# source_eagle.net
KiCad netlist of a schematic drawn in EAGLE
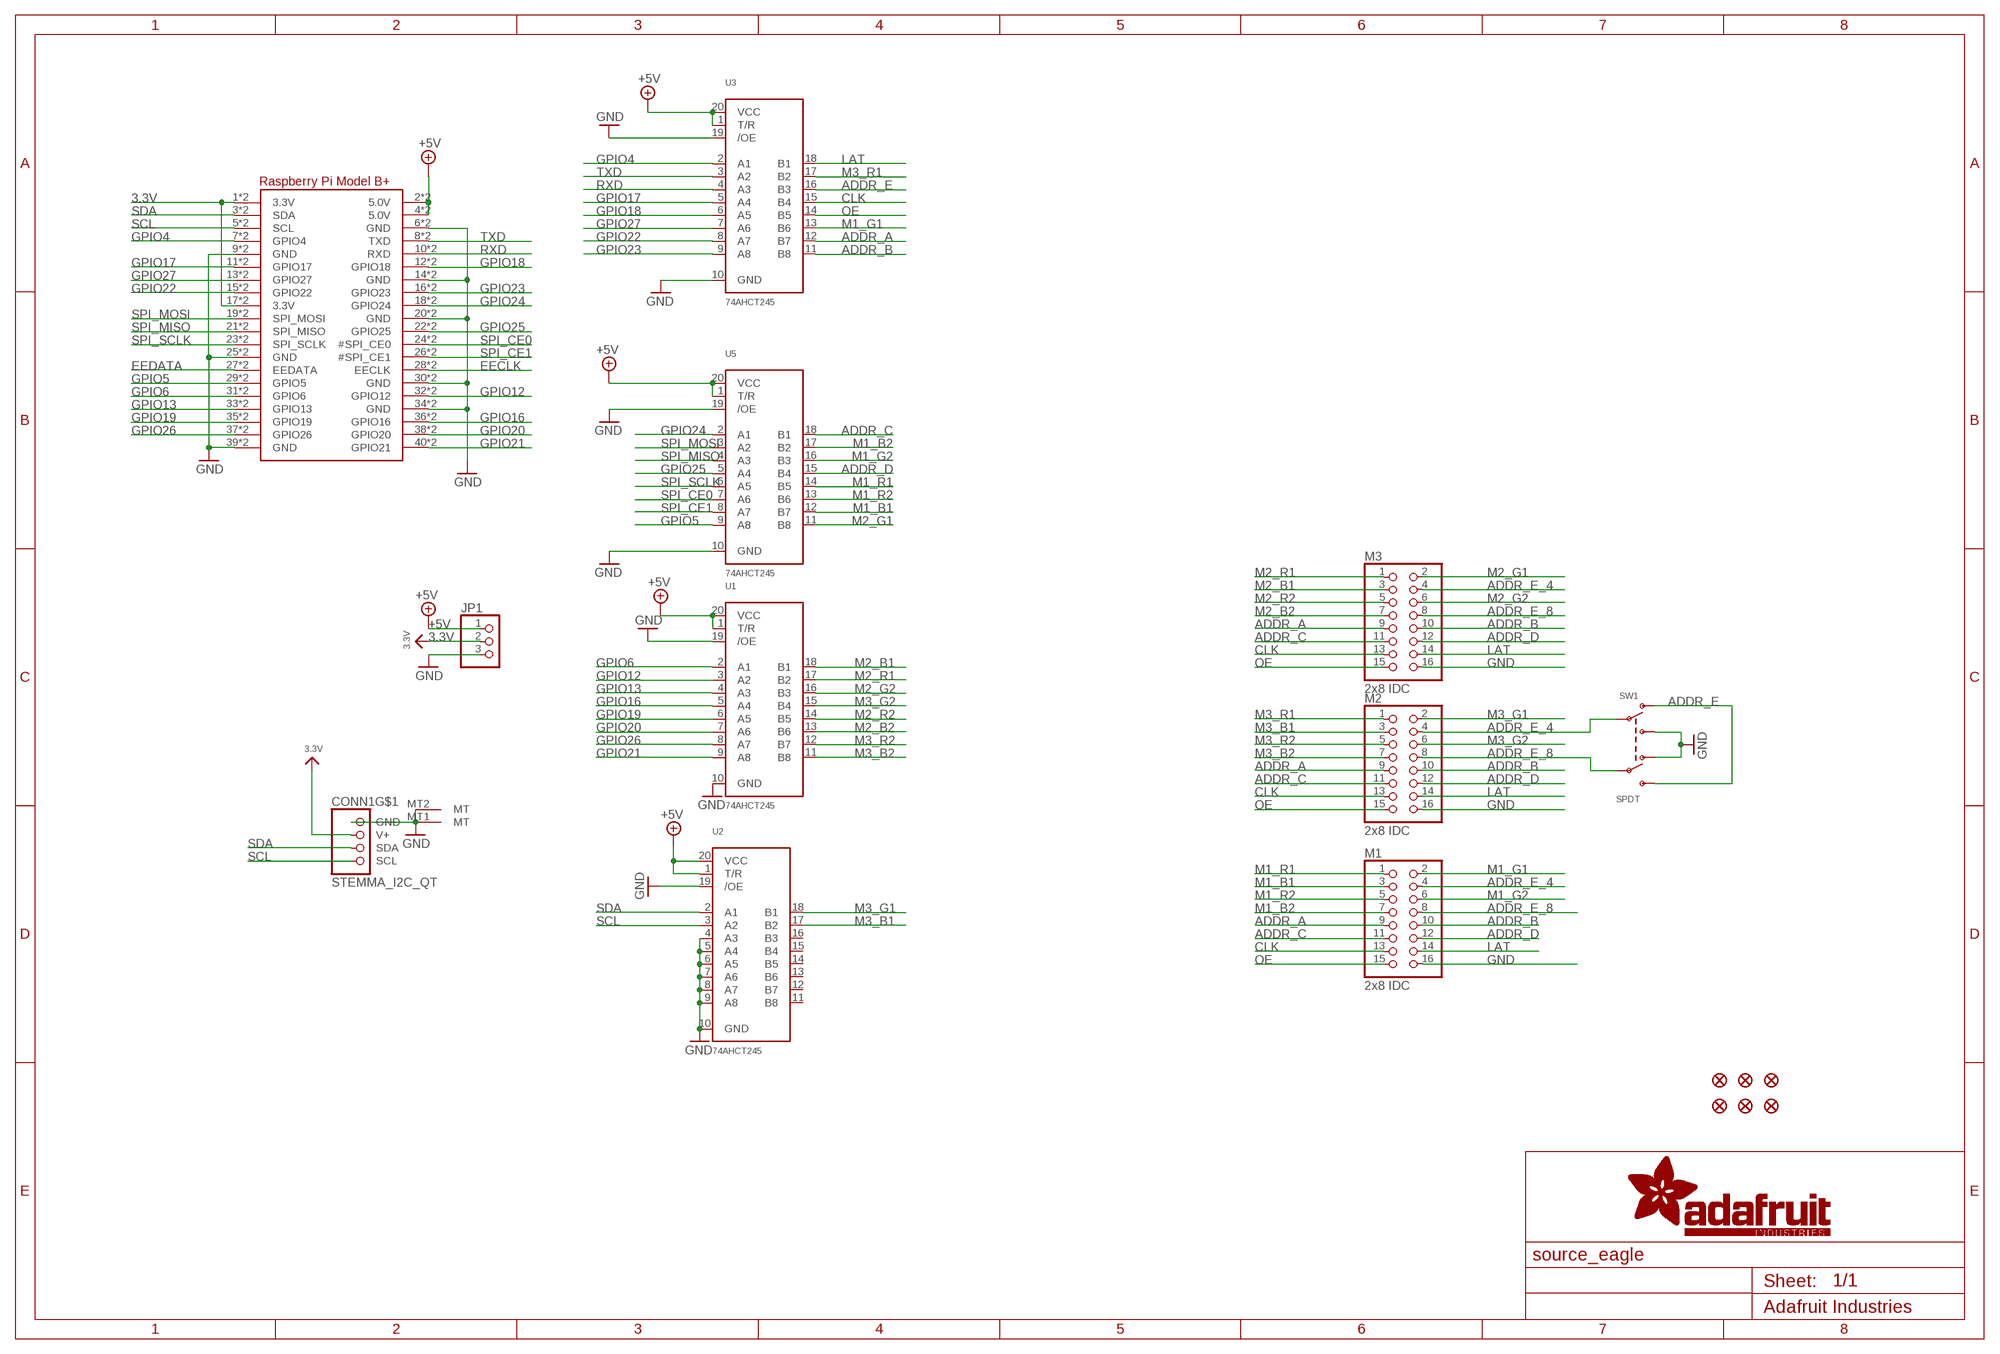
[diagram p0: schematic, sheet 1]

(export (version "E")
  (design (tool "Eeschema 10.0.6"))
  (components
    (comp (ref "CONN1")
      (value "STEMMA_I2C_QT")
      (footprint "eagle-import:JST_SH4")
      (libsource (lib "eagle-import") (part "STEMMA_I2C_QT"))
    )
    (comp (ref "FID1")
      (value "FIDUCIAL_1MM")
      (footprint "eagle-import:FIDUCIAL_1MM")
      (libsource (lib "eagle-import") (part "FIDUCIAL_1MM"))
    )
    (comp (ref "FID2")
      (value "FIDUCIAL_1MM")
      (footprint "eagle-import:FIDUCIAL_1MM")
      (libsource (lib "eagle-import") (part "FIDUCIAL_1MM"))
    )
    (comp (ref "FID3")
      (value "FIDUCIAL_1MM")
      (footprint "eagle-import:FIDUCIAL_1MM")
      (libsource (lib "eagle-import") (part "FIDUCIAL_1MM"))
    )
    (comp (ref "FID4")
      (value "FIDUCIAL_1MM")
      (footprint "eagle-import:FIDUCIAL_1MM")
      (libsource (lib "eagle-import") (part "FIDUCIAL_1MM"))
    )
    (comp (ref "FID5")
      (value "FIDUCIAL_1MM")
      (footprint "eagle-import:FIDUCIAL_1MM")
      (libsource (lib "eagle-import") (part "FIDUCIAL_1MM"))
    )
    (comp (ref "FID6")
      (value "FIDUCIAL_1MM")
      (footprint "eagle-import:FIDUCIAL_1MM")
      (libsource (lib "eagle-import") (part "FIDUCIAL_1MM"))
    )
    (comp (ref "JP1")
      (value "HEADER-1X376MIL")
      (footprint "eagle-import:1X03_ROUND_76")
      (libsource (lib "eagle-import") (part "HEADER-1X376MIL"))
    )
    (comp (ref "M1")
      (value "2x8 IDC")
      (footprint "eagle-import:2X08_SHROUDED")
      (libsource (lib "eagle-import") (part "HEADER-2X8_SHROUDED"))
    )
    (comp (ref "M2")
      (value "2x8 IDC")
      (footprint "eagle-import:2X08_SHROUDED")
      (libsource (lib "eagle-import") (part "HEADER-2X8_SHROUDED"))
    )
    (comp (ref "M3")
      (value "2x8 IDC")
      (footprint "eagle-import:2X08_SHROUDED")
      (libsource (lib "eagle-import") (part "HEADER-2X8_SHROUDED"))
    )
    (comp (ref "RPI1")
      (value "RASPBERRYPI_BPLUS_2X20_THMSMT")
      (footprint "eagle-import:RASPI_2X20_THMSMT")
      (libsource (lib "eagle-import") (part "RASPBERRYPI_BPLUS_2X20_THMSMT"))
    )
    (comp (ref "SW1")
      (value "SPDT")
      (footprint "eagle-import:EG1390")
      (libsource (lib "eagle-import") (part "SWITCH_DPDTEG1390"))
    )
    (comp (ref "U1")
      (value "74AHCT245")
      (footprint "eagle-import:TSSOP20")
      (libsource (lib "eagle-import") (part "74LCX245_TSSOP20"))
    )
    (comp (ref "U2")
      (value "74AHCT245")
      (footprint "eagle-import:TSSOP20")
      (libsource (lib "eagle-import") (part "74LCX245_TSSOP20"))
    )
    (comp (ref "U3")
      (value "74AHCT245")
      (footprint "eagle-import:TSSOP20")
      (libsource (lib "eagle-import") (part "74LCX245_TSSOP20"))
    )
    (comp (ref "U5")
      (value "74AHCT245")
      (footprint "eagle-import:TSSOP20")
      (libsource (lib "eagle-import") (part "74LCX245_TSSOP20"))
    )
  )
  (nets
    (net (code "1") (name "+5V") (class "Default")
      (node (ref "JP1") (pin "1") (pinfunction "1_1") (pintype "passive"))
      (node (ref "RPI1") (pin "2") (pinfunction "5.0V_2") (pintype "power_in"))
      (node (ref "RPI1") (pin "4") (pinfunction "5.0V_4") (pintype "power_in"))
      (node (ref "RPI1") (pin "S2") (pinfunction "5.0V_S2") (pintype "power_in"))
      (node (ref "RPI1") (pin "S4") (pinfunction "5.0V_S4") (pintype "power_in"))
      (node (ref "U1") (pin "1") (pinfunction "T/R_1") (pintype "bidirectional"))
      (node (ref "U1") (pin "20") (pinfunction "VCC_20") (pintype "bidirectional"))
      (node (ref "U2") (pin "1") (pinfunction "T/R_1") (pintype "bidirectional"))
      (node (ref "U2") (pin "20") (pinfunction "VCC_20") (pintype "bidirectional"))
      (node (ref "U3") (pin "1") (pinfunction "T/R_1") (pintype "bidirectional"))
      (node (ref "U3") (pin "20") (pinfunction "VCC_20") (pintype "bidirectional"))
      (node (ref "U5") (pin "1") (pinfunction "T/R_1") (pintype "bidirectional"))
      (node (ref "U5") (pin "20") (pinfunction "VCC_20") (pintype "bidirectional"))
    )
    (net (code "2") (name "/ADDR_A") (class "Default")
      (node (ref "M1") (pin "9") (pinfunction "9_9") (pintype "passive"))
      (node (ref "M2") (pin "9") (pinfunction "9_9") (pintype "passive"))
      (node (ref "M3") (pin "9") (pinfunction "9_9") (pintype "passive"))
      (node (ref "U3") (pin "12") (pinfunction "B7_12") (pintype "bidirectional"))
    )
    (net (code "3") (name "/ADDR_B") (class "Default")
      (node (ref "M1") (pin "10") (pinfunction "10_10") (pintype "passive"))
      (node (ref "M2") (pin "10") (pinfunction "10_10") (pintype "passive"))
      (node (ref "M3") (pin "10") (pinfunction "10_10") (pintype "passive"))
      (node (ref "U3") (pin "11") (pinfunction "B8_11") (pintype "bidirectional"))
    )
    (net (code "4") (name "/ADDR_C") (class "Default")
      (node (ref "M1") (pin "11") (pinfunction "11_11") (pintype "passive"))
      (node (ref "M2") (pin "11") (pinfunction "11_11") (pintype "passive"))
      (node (ref "M3") (pin "11") (pinfunction "11_11") (pintype "passive"))
      (node (ref "U5") (pin "18") (pinfunction "B1_18") (pintype "bidirectional"))
    )
    (net (code "5") (name "/ADDR_D") (class "Default")
      (node (ref "M1") (pin "12") (pinfunction "12_12") (pintype "passive"))
      (node (ref "M2") (pin "12") (pinfunction "12_12") (pintype "passive"))
      (node (ref "M3") (pin "12") (pinfunction "12_12") (pintype "passive"))
      (node (ref "U5") (pin "15") (pinfunction "B4_15") (pintype "bidirectional"))
    )
    (net (code "6") (name "/ADDR_E") (class "Default")
      (node (ref "SW1") (pin "O1") (pinfunction "O1_O1") (pintype "passive"))
      (node (ref "SW1") (pin "S2") (pinfunction "S2_S2") (pintype "passive"))
      (node (ref "U3") (pin "16") (pinfunction "B3_16") (pintype "bidirectional"))
    )
    (net (code "7") (name "/ADDR_E_4") (class "Default")
      (node (ref "M1") (pin "4") (pinfunction "4_4") (pintype "passive"))
      (node (ref "M2") (pin "4") (pinfunction "4_4") (pintype "passive"))
      (node (ref "M3") (pin "4") (pinfunction "4_4") (pintype "passive"))
      (node (ref "SW1") (pin "P1") (pinfunction "P1_P1") (pintype "passive"))
    )
    (net (code "8") (name "/ADDR_E_8") (class "Default")
      (node (ref "M1") (pin "8") (pinfunction "8_8") (pintype "passive"))
      (node (ref "M2") (pin "8") (pinfunction "8_8") (pintype "passive"))
      (node (ref "M3") (pin "8") (pinfunction "8_8") (pintype "passive"))
      (node (ref "SW1") (pin "P2") (pinfunction "P2_P2") (pintype "passive"))
    )
    (net (code "9") (name "/CLK") (class "Default")
      (node (ref "M1") (pin "13") (pinfunction "13_13") (pintype "passive"))
      (node (ref "M2") (pin "13") (pinfunction "13_13") (pintype "passive"))
      (node (ref "M3") (pin "13") (pinfunction "13_13") (pintype "passive"))
      (node (ref "U3") (pin "15") (pinfunction "B4_15") (pintype "bidirectional"))
    )
    (net (code "10") (name "/EECLK") (class "Default")
      (node (ref "RPI1") (pin "28") (pinfunction "EECLK_28") (pintype "bidirectional"))
      (node (ref "RPI1") (pin "S28") (pinfunction "EECLK_S28") (pintype "bidirectional"))
    )
    (net (code "11") (name "/EEDATA") (class "Default")
      (node (ref "RPI1") (pin "27") (pinfunction "EEDATA_27") (pintype "bidirectional"))
      (node (ref "RPI1") (pin "S27") (pinfunction "EEDATA_S27") (pintype "bidirectional"))
    )
    (net (code "12") (name "/GPIO4") (class "Default")
      (node (ref "RPI1") (pin "7") (pinfunction "GPIO4_7") (pintype "bidirectional"))
      (node (ref "RPI1") (pin "S7") (pinfunction "GPIO4_S7") (pintype "bidirectional"))
      (node (ref "U3") (pin "2") (pinfunction "A1_2") (pintype "bidirectional"))
    )
    (net (code "13") (name "/GPIO5") (class "Default")
      (node (ref "RPI1") (pin "29") (pinfunction "GPIO5_29") (pintype "bidirectional"))
      (node (ref "RPI1") (pin "S29") (pinfunction "GPIO5_S29") (pintype "bidirectional"))
      (node (ref "U5") (pin "9") (pinfunction "A8_9") (pintype "bidirectional"))
    )
    (net (code "14") (name "/GPIO6") (class "Default")
      (node (ref "RPI1") (pin "31") (pinfunction "GPIO6_31") (pintype "bidirectional"))
      (node (ref "RPI1") (pin "S31") (pinfunction "GPIO6_S31") (pintype "bidirectional"))
      (node (ref "U1") (pin "2") (pinfunction "A1_2") (pintype "bidirectional"))
    )
    (net (code "15") (name "/GPIO12") (class "Default")
      (node (ref "RPI1") (pin "32") (pinfunction "GPIO12_32") (pintype "bidirectional"))
      (node (ref "RPI1") (pin "S32") (pinfunction "GPIO12_S32") (pintype "bidirectional"))
      (node (ref "U1") (pin "3") (pinfunction "A2_3") (pintype "bidirectional"))
    )
    (net (code "16") (name "/GPIO13") (class "Default")
      (node (ref "RPI1") (pin "33") (pinfunction "GPIO13_33") (pintype "bidirectional"))
      (node (ref "RPI1") (pin "S33") (pinfunction "GPIO13_S33") (pintype "bidirectional"))
      (node (ref "U1") (pin "4") (pinfunction "A3_4") (pintype "bidirectional"))
    )
    (net (code "17") (name "/GPIO16") (class "Default")
      (node (ref "RPI1") (pin "36") (pinfunction "GPIO16_36") (pintype "bidirectional"))
      (node (ref "RPI1") (pin "S36") (pinfunction "GPIO16_S36") (pintype "bidirectional"))
      (node (ref "U1") (pin "5") (pinfunction "A4_5") (pintype "bidirectional"))
    )
    (net (code "18") (name "/GPIO17") (class "Default")
      (node (ref "RPI1") (pin "11") (pinfunction "GPIO17_11") (pintype "bidirectional"))
      (node (ref "RPI1") (pin "S11") (pinfunction "GPIO17_S11") (pintype "bidirectional"))
      (node (ref "U3") (pin "5") (pinfunction "A4_5") (pintype "bidirectional"))
    )
    (net (code "19") (name "/GPIO18") (class "Default")
      (node (ref "RPI1") (pin "12") (pinfunction "GPIO18_12") (pintype "bidirectional"))
      (node (ref "RPI1") (pin "S12") (pinfunction "GPIO18_S12") (pintype "bidirectional"))
      (node (ref "U3") (pin "6") (pinfunction "A5_6") (pintype "bidirectional"))
    )
    (net (code "20") (name "/GPIO19") (class "Default")
      (node (ref "RPI1") (pin "35") (pinfunction "GPIO19_35") (pintype "bidirectional"))
      (node (ref "RPI1") (pin "S35") (pinfunction "GPIO19_S35") (pintype "bidirectional"))
      (node (ref "U1") (pin "6") (pinfunction "A5_6") (pintype "bidirectional"))
    )
    (net (code "21") (name "/GPIO20") (class "Default")
      (node (ref "RPI1") (pin "38") (pinfunction "GPIO20_38") (pintype "bidirectional"))
      (node (ref "RPI1") (pin "S38") (pinfunction "GPIO20_S38") (pintype "bidirectional"))
      (node (ref "U1") (pin "7") (pinfunction "A6_7") (pintype "bidirectional"))
    )
    (net (code "22") (name "/GPIO21") (class "Default")
      (node (ref "RPI1") (pin "40") (pinfunction "GPIO21_40") (pintype "bidirectional"))
      (node (ref "RPI1") (pin "S40") (pinfunction "GPIO21_S40") (pintype "bidirectional"))
      (node (ref "U1") (pin "9") (pinfunction "A8_9") (pintype "bidirectional"))
    )
    (net (code "23") (name "/GPIO22") (class "Default")
      (node (ref "RPI1") (pin "15") (pinfunction "GPIO22_15") (pintype "bidirectional"))
      (node (ref "RPI1") (pin "S15") (pinfunction "GPIO22_S15") (pintype "bidirectional"))
      (node (ref "U3") (pin "8") (pinfunction "A7_8") (pintype "bidirectional"))
    )
    (net (code "24") (name "/GPIO23") (class "Default")
      (node (ref "RPI1") (pin "16") (pinfunction "GPIO23_16") (pintype "bidirectional"))
      (node (ref "RPI1") (pin "S16") (pinfunction "GPIO23_S16") (pintype "bidirectional"))
      (node (ref "U3") (pin "9") (pinfunction "A8_9") (pintype "bidirectional"))
    )
    (net (code "25") (name "/GPIO24") (class "Default")
      (node (ref "RPI1") (pin "18") (pinfunction "GPIO24_18") (pintype "bidirectional"))
      (node (ref "RPI1") (pin "S18") (pinfunction "GPIO24_S18") (pintype "bidirectional"))
      (node (ref "U5") (pin "2") (pinfunction "A1_2") (pintype "bidirectional"))
    )
    (net (code "26") (name "/GPIO25") (class "Default")
      (node (ref "RPI1") (pin "22") (pinfunction "GPIO25_22") (pintype "bidirectional"))
      (node (ref "RPI1") (pin "S22") (pinfunction "GPIO25_S22") (pintype "bidirectional"))
      (node (ref "U5") (pin "5") (pinfunction "A4_5") (pintype "bidirectional"))
    )
    (net (code "27") (name "/GPIO26") (class "Default")
      (node (ref "RPI1") (pin "37") (pinfunction "GPIO26_37") (pintype "bidirectional"))
      (node (ref "RPI1") (pin "S37") (pinfunction "GPIO26_S37") (pintype "bidirectional"))
      (node (ref "U1") (pin "8") (pinfunction "A7_8") (pintype "bidirectional"))
    )
    (net (code "28") (name "/GPIO27") (class "Default")
      (node (ref "RPI1") (pin "13") (pinfunction "GPIO27_13") (pintype "bidirectional"))
      (node (ref "RPI1") (pin "S13") (pinfunction "GPIO27_S13") (pintype "bidirectional"))
      (node (ref "U3") (pin "7") (pinfunction "A6_7") (pintype "bidirectional"))
    )
    (net (code "29") (name "/LAT") (class "Default")
      (node (ref "M1") (pin "14") (pinfunction "14_14") (pintype "passive"))
      (node (ref "M2") (pin "14") (pinfunction "14_14") (pintype "passive"))
      (node (ref "M3") (pin "14") (pinfunction "14_14") (pintype "passive"))
      (node (ref "U3") (pin "18") (pinfunction "B1_18") (pintype "bidirectional"))
    )
    (net (code "30") (name "/M1_B1") (class "Default")
      (node (ref "M1") (pin "3") (pinfunction "3_3") (pintype "passive"))
      (node (ref "U5") (pin "12") (pinfunction "B7_12") (pintype "bidirectional"))
    )
    (net (code "31") (name "/M1_B2") (class "Default")
      (node (ref "M1") (pin "7") (pinfunction "7_7") (pintype "passive"))
      (node (ref "U5") (pin "17") (pinfunction "B2_17") (pintype "bidirectional"))
    )
    (net (code "32") (name "/M1_G1") (class "Default")
      (node (ref "M1") (pin "2") (pinfunction "2_2") (pintype "passive"))
      (node (ref "U3") (pin "13") (pinfunction "B6_13") (pintype "bidirectional"))
    )
    (net (code "33") (name "/M1_G2") (class "Default")
      (node (ref "M1") (pin "6") (pinfunction "6_6") (pintype "passive"))
      (node (ref "U5") (pin "16") (pinfunction "B3_16") (pintype "bidirectional"))
    )
    (net (code "34") (name "/M1_R1") (class "Default")
      (node (ref "M1") (pin "1") (pinfunction "1_1") (pintype "passive"))
      (node (ref "U5") (pin "14") (pinfunction "B5_14") (pintype "bidirectional"))
    )
    (net (code "35") (name "/M1_R2") (class "Default")
      (node (ref "M1") (pin "5") (pinfunction "5_5") (pintype "passive"))
      (node (ref "U5") (pin "13") (pinfunction "B6_13") (pintype "bidirectional"))
    )
    (net (code "36") (name "/M2_B1") (class "Default")
      (node (ref "M3") (pin "3") (pinfunction "3_3") (pintype "passive"))
      (node (ref "U1") (pin "18") (pinfunction "B1_18") (pintype "bidirectional"))
    )
    (net (code "37") (name "/M2_B2") (class "Default")
      (node (ref "M3") (pin "7") (pinfunction "7_7") (pintype "passive"))
      (node (ref "U1") (pin "13") (pinfunction "B6_13") (pintype "bidirectional"))
    )
    (net (code "38") (name "/M2_G1") (class "Default")
      (node (ref "M3") (pin "2") (pinfunction "2_2") (pintype "passive"))
      (node (ref "U5") (pin "11") (pinfunction "B8_11") (pintype "bidirectional"))
    )
    (net (code "39") (name "/M2_G2") (class "Default")
      (node (ref "M3") (pin "6") (pinfunction "6_6") (pintype "passive"))
      (node (ref "U1") (pin "16") (pinfunction "B3_16") (pintype "bidirectional"))
    )
    (net (code "40") (name "/M2_R1") (class "Default")
      (node (ref "M3") (pin "1") (pinfunction "1_1") (pintype "passive"))
      (node (ref "U1") (pin "17") (pinfunction "B2_17") (pintype "bidirectional"))
    )
    (net (code "41") (name "/M2_R2") (class "Default")
      (node (ref "M3") (pin "5") (pinfunction "5_5") (pintype "passive"))
      (node (ref "U1") (pin "14") (pinfunction "B5_14") (pintype "bidirectional"))
    )
    (net (code "42") (name "/M3_B1") (class "Default")
      (node (ref "M2") (pin "3") (pinfunction "3_3") (pintype "passive"))
      (node (ref "U2") (pin "17") (pinfunction "B2_17") (pintype "bidirectional"))
    )
    (net (code "43") (name "/M3_B2") (class "Default")
      (node (ref "M2") (pin "7") (pinfunction "7_7") (pintype "passive"))
      (node (ref "U1") (pin "11") (pinfunction "B8_11") (pintype "bidirectional"))
    )
    (net (code "44") (name "/M3_G1") (class "Default")
      (node (ref "M2") (pin "2") (pinfunction "2_2") (pintype "passive"))
      (node (ref "U2") (pin "18") (pinfunction "B1_18") (pintype "bidirectional"))
    )
    (net (code "45") (name "/M3_G2") (class "Default")
      (node (ref "M2") (pin "6") (pinfunction "6_6") (pintype "passive"))
      (node (ref "U1") (pin "15") (pinfunction "B4_15") (pintype "bidirectional"))
    )
    (net (code "46") (name "/M3_R1") (class "Default")
      (node (ref "M2") (pin "1") (pinfunction "1_1") (pintype "passive"))
      (node (ref "U3") (pin "17") (pinfunction "B2_17") (pintype "bidirectional"))
    )
    (net (code "47") (name "/M3_R2") (class "Default")
      (node (ref "M2") (pin "5") (pinfunction "5_5") (pintype "passive"))
      (node (ref "U1") (pin "12") (pinfunction "B7_12") (pintype "bidirectional"))
    )
    (net (code "48") (name "/OE") (class "Default")
      (node (ref "M1") (pin "15") (pinfunction "15_15") (pintype "passive"))
      (node (ref "M2") (pin "15") (pinfunction "15_15") (pintype "passive"))
      (node (ref "M3") (pin "15") (pinfunction "15_15") (pintype "passive"))
      (node (ref "U3") (pin "14") (pinfunction "B5_14") (pintype "bidirectional"))
    )
    (net (code "49") (name "/RXD") (class "Default")
      (node (ref "RPI1") (pin "10") (pinfunction "RXD_10") (pintype "bidirectional"))
      (node (ref "RPI1") (pin "S10") (pinfunction "RXD_S10") (pintype "bidirectional"))
      (node (ref "U3") (pin "4") (pinfunction "A3_4") (pintype "bidirectional"))
    )
    (net (code "50") (name "/SCL") (class "Default")
      (node (ref "CONN1") (pin "4") (pinfunction "SCL_4") (pintype "passive"))
      (node (ref "RPI1") (pin "5") (pinfunction "SCL_5") (pintype "bidirectional"))
      (node (ref "RPI1") (pin "S5") (pinfunction "SCL_S5") (pintype "bidirectional"))
      (node (ref "U2") (pin "3") (pinfunction "A2_3") (pintype "bidirectional"))
    )
    (net (code "51") (name "/SDA") (class "Default")
      (node (ref "CONN1") (pin "3") (pinfunction "SDA_3") (pintype "passive"))
      (node (ref "RPI1") (pin "3") (pinfunction "SDA_3") (pintype "bidirectional"))
      (node (ref "RPI1") (pin "S3") (pinfunction "SDA_S3") (pintype "bidirectional"))
      (node (ref "U2") (pin "2") (pinfunction "A1_2") (pintype "bidirectional"))
    )
    (net (code "52") (name "/SPI_CE0") (class "Default")
      (node (ref "RPI1") (pin "24") (pinfunction "#SPI_CE0_24") (pintype "bidirectional"))
      (node (ref "RPI1") (pin "S24") (pinfunction "#SPI_CE0_S24") (pintype "bidirectional"))
      (node (ref "U5") (pin "7") (pinfunction "A6_7") (pintype "bidirectional"))
    )
    (net (code "53") (name "/SPI_CE1") (class "Default")
      (node (ref "RPI1") (pin "26") (pinfunction "#SPI_CE1_26") (pintype "bidirectional"))
      (node (ref "RPI1") (pin "S26") (pinfunction "#SPI_CE1_S26") (pintype "bidirectional"))
      (node (ref "U5") (pin "8") (pinfunction "A7_8") (pintype "bidirectional"))
    )
    (net (code "54") (name "/SPI_MISO") (class "Default")
      (node (ref "RPI1") (pin "21") (pinfunction "SPI_MISO_21") (pintype "bidirectional"))
      (node (ref "RPI1") (pin "S21") (pinfunction "SPI_MISO_S21") (pintype "bidirectional"))
      (node (ref "U5") (pin "4") (pinfunction "A3_4") (pintype "bidirectional"))
    )
    (net (code "55") (name "/SPI_MOSI") (class "Default")
      (node (ref "RPI1") (pin "19") (pinfunction "SPI_MOSI_19") (pintype "bidirectional"))
      (node (ref "RPI1") (pin "S19") (pinfunction "SPI_MOSI_S19") (pintype "bidirectional"))
      (node (ref "U5") (pin "3") (pinfunction "A2_3") (pintype "bidirectional"))
    )
    (net (code "56") (name "/SPI_SCLK") (class "Default")
      (node (ref "RPI1") (pin "23") (pinfunction "SPI_SCLK_23") (pintype "bidirectional"))
      (node (ref "RPI1") (pin "S23") (pinfunction "SPI_SCLK_S23") (pintype "bidirectional"))
      (node (ref "U5") (pin "6") (pinfunction "A5_6") (pintype "bidirectional"))
    )
    (net (code "57") (name "/TXD") (class "Default")
      (node (ref "RPI1") (pin "8") (pinfunction "TXD_8") (pintype "bidirectional"))
      (node (ref "RPI1") (pin "S8") (pinfunction "TXD_S8") (pintype "bidirectional"))
      (node (ref "U3") (pin "3") (pinfunction "A2_3") (pintype "bidirectional"))
    )
    (net (code "58") (name "3.3V") (class "Default")
      (node (ref "CONN1") (pin "2") (pinfunction "V+_2") (pintype "passive"))
      (node (ref "JP1") (pin "2") (pinfunction "2_2") (pintype "passive"))
      (node (ref "RPI1") (pin "1") (pinfunction "3.3V_1") (pintype "power_in"))
      (node (ref "RPI1") (pin "17") (pinfunction "3.3V_17") (pintype "power_in"))
      (node (ref "RPI1") (pin "S1") (pinfunction "3.3V_S1") (pintype "power_in"))
      (node (ref "RPI1") (pin "S17") (pinfunction "3.3V_S17") (pintype "power_in"))
    )
    (net (code "59") (name "GND") (class "Default")
      (node (ref "CONN1") (pin "1") (pinfunction "GND_1") (pintype "passive"))
      (node (ref "CONN1") (pin "MT1") (pinfunction "MT_MT1") (pintype "bidirectional"))
      (node (ref "CONN1") (pin "MT2") (pinfunction "MT_MT2") (pintype "bidirectional"))
      (node (ref "JP1") (pin "3") (pinfunction "3_3") (pintype "passive"))
      (node (ref "M1") (pin "16") (pinfunction "16_16") (pintype "passive"))
      (node (ref "M2") (pin "16") (pinfunction "16_16") (pintype "passive"))
      (node (ref "M3") (pin "16") (pinfunction "16_16") (pintype "passive"))
      (node (ref "RPI1") (pin "14") (pinfunction "GND_14") (pintype "power_in"))
      (node (ref "RPI1") (pin "20") (pinfunction "GND_20") (pintype "power_in"))
      (node (ref "RPI1") (pin "25") (pinfunction "GND_25") (pintype "power_in"))
      (node (ref "RPI1") (pin "30") (pinfunction "GND_30") (pintype "power_in"))
      (node (ref "RPI1") (pin "34") (pinfunction "GND_34") (pintype "power_in"))
      (node (ref "RPI1") (pin "39") (pinfunction "GND_39") (pintype "power_in"))
      (node (ref "RPI1") (pin "6") (pinfunction "GND_6") (pintype "power_in"))
      (node (ref "RPI1") (pin "9") (pinfunction "GND_9") (pintype "power_in"))
      (node (ref "RPI1") (pin "S14") (pinfunction "GND_S14") (pintype "power_in"))
      (node (ref "RPI1") (pin "S20") (pinfunction "GND_S20") (pintype "power_in"))
      (node (ref "RPI1") (pin "S25") (pinfunction "GND_S25") (pintype "power_in"))
      (node (ref "RPI1") (pin "S30") (pinfunction "GND_S30") (pintype "power_in"))
      (node (ref "RPI1") (pin "S34") (pinfunction "GND_S34") (pintype "power_in"))
      (node (ref "RPI1") (pin "S39") (pinfunction "GND_S39") (pintype "power_in"))
      (node (ref "RPI1") (pin "S6") (pinfunction "GND_S6") (pintype "power_in"))
      (node (ref "RPI1") (pin "S9") (pinfunction "GND_S9") (pintype "power_in"))
      (node (ref "SW1") (pin "O2") (pinfunction "O2_O2") (pintype "passive"))
      (node (ref "SW1") (pin "S1") (pinfunction "S1_S1") (pintype "passive"))
      (node (ref "U1") (pin "10") (pinfunction "GND_10") (pintype "bidirectional"))
      (node (ref "U1") (pin "19") (pinfunction "/OE_19") (pintype "bidirectional"))
      (node (ref "U2") (pin "10") (pinfunction "GND_10") (pintype "bidirectional"))
      (node (ref "U2") (pin "19") (pinfunction "/OE_19") (pintype "bidirectional"))
      (node (ref "U2") (pin "4") (pinfunction "A3_4") (pintype "bidirectional"))
      (node (ref "U2") (pin "5") (pinfunction "A4_5") (pintype "bidirectional"))
      (node (ref "U2") (pin "6") (pinfunction "A5_6") (pintype "bidirectional"))
      (node (ref "U2") (pin "7") (pinfunction "A6_7") (pintype "bidirectional"))
      (node (ref "U2") (pin "8") (pinfunction "A7_8") (pintype "bidirectional"))
      (node (ref "U2") (pin "9") (pinfunction "A8_9") (pintype "bidirectional"))
      (node (ref "U3") (pin "10") (pinfunction "GND_10") (pintype "bidirectional"))
      (node (ref "U3") (pin "19") (pinfunction "/OE_19") (pintype "bidirectional"))
      (node (ref "U5") (pin "10") (pinfunction "GND_10") (pintype "bidirectional"))
      (node (ref "U5") (pin "19") (pinfunction "/OE_19") (pintype "bidirectional"))
    )
    (net (code "60") (name "unconnected-(U2-B3-Pad16)") (class "Default")
      (node (ref "U2") (pin "16") (pinfunction "B3_16") (pintype "bidirectional"))
    )
    (net (code "61") (name "unconnected-(U2-B4-Pad15)") (class "Default")
      (node (ref "U2") (pin "15") (pinfunction "B4_15") (pintype "bidirectional"))
    )
    (net (code "62") (name "unconnected-(U2-B5-Pad14)") (class "Default")
      (node (ref "U2") (pin "14") (pinfunction "B5_14") (pintype "bidirectional"))
    )
    (net (code "63") (name "unconnected-(U2-B6-Pad13)") (class "Default")
      (node (ref "U2") (pin "13") (pinfunction "B6_13") (pintype "bidirectional"))
    )
    (net (code "64") (name "unconnected-(U2-B7-Pad12)") (class "Default")
      (node (ref "U2") (pin "12") (pinfunction "B7_12") (pintype "bidirectional"))
    )
    (net (code "65") (name "unconnected-(U2-B8-Pad11)") (class "Default")
      (node (ref "U2") (pin "11") (pinfunction "B8_11") (pintype "bidirectional"))
    )
  )
)
